# Evergreen.net
KiCad netlist of a schematic drawn in EAGLE
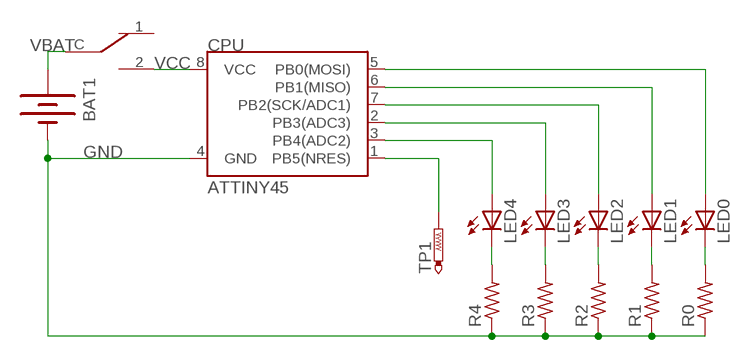
[diagram p0: schematic, sheet 1]

(export (version "E")
  (design (tool "Eeschema 10.0.6"))
  (components
    (comp (ref "BAT1")
      (value "BATTERY20SMD")
      (footprint "eagle-import:BATTCON_20MM")
      (libsource (lib "eagle-import") (part "BATTERY20SMD"))
    )
    (comp (ref "CPU")
      (value "ATTINY45")
      (footprint "eagle-import:SO08-EIAJ")
      (libsource (lib "eagle-import") (part "ATTINY45"))
    )
    (comp (ref "LED0")
      (value "LEDCHIP-LED0805")
      (footprint "eagle-import:CHIP-LED0805")
      (libsource (lib "eagle-import") (part "LEDCHIP-LED0805"))
    )
    (comp (ref "LED1")
      (value "LEDCHIP-LED0805")
      (footprint "eagle-import:CHIP-LED0805")
      (libsource (lib "eagle-import") (part "LEDCHIP-LED0805"))
    )
    (comp (ref "LED2")
      (value "LEDCHIP-LED0805")
      (footprint "eagle-import:CHIP-LED0805")
      (libsource (lib "eagle-import") (part "LEDCHIP-LED0805"))
    )
    (comp (ref "LED3")
      (value "LEDCHIP-LED0805")
      (footprint "eagle-import:CHIP-LED0805")
      (libsource (lib "eagle-import") (part "LEDCHIP-LED0805"))
    )
    (comp (ref "LED4")
      (value "LEDCHIP-LED0805")
      (footprint "eagle-import:CHIP-LED0805")
      (libsource (lib "eagle-import") (part "LEDCHIP-LED0805"))
    )
    (comp (ref "R0")
      (value "R-US_M0805")
      (footprint "eagle-import:M0805")
      (libsource (lib "eagle-import") (part "R-US_M0805"))
    )
    (comp (ref "R1")
      (value "R-US_M0805")
      (footprint "eagle-import:M0805")
      (libsource (lib "eagle-import") (part "R-US_M0805"))
    )
    (comp (ref "R2")
      (value "R-US_M0805")
      (footprint "eagle-import:M0805")
      (libsource (lib "eagle-import") (part "R-US_M0805"))
    )
    (comp (ref "R3")
      (value "R-US_M0805")
      (footprint "eagle-import:M0805")
      (libsource (lib "eagle-import") (part "R-US_M0805"))
    )
    (comp (ref "R4")
      (value "R-US_M0805")
      (footprint "eagle-import:M0805")
      (libsource (lib "eagle-import") (part "R-US_M0805"))
    )
    (comp (ref "SWITCH")
      (value "SWITCH-SPDT")
      (footprint "eagle-import:SSAJ120100")
      (libsource (lib "eagle-import") (part "SWITCH-SPDT"))
    )
    (comp (ref "TP1")
      (value "PTR1B2,54")
      (footprint "eagle-import:B2,54")
      (libsource (lib "eagle-import") (part "PTR1B2,54"))
    )
  )
  (nets
    (net (code "1") (name "/GND") (class "Default")
      (node (ref "BAT1") (pin "2") (pinfunction "-_2") (pintype "power_in"))
      (node (ref "CPU") (pin "4") (pinfunction "GND_4") (pintype "bidirectional"))
      (node (ref "R0") (pin "1") (pinfunction "1_1") (pintype "passive"))
      (node (ref "R1") (pin "1") (pinfunction "1_1") (pintype "passive"))
      (node (ref "R2") (pin "1") (pinfunction "1_1") (pintype "passive"))
      (node (ref "R3") (pin "1") (pinfunction "1_1") (pintype "passive"))
      (node (ref "R4") (pin "1") (pinfunction "1_1") (pintype "passive"))
    )
    (net (code "2") (name "/VBAT") (class "Default")
      (node (ref "BAT1") (pin "1") (pinfunction "+_1") (pintype "power_in"))
      (node (ref "BAT1") (pin "3") (pinfunction "+_3") (pintype "power_in"))
      (node (ref "SWITCH") (pin "C") (pinfunction "C_C") (pintype "bidirectional"))
    )
    (net (code "3") (name "/VCC") (class "Default")
      (node (ref "CPU") (pin "8") (pinfunction "VCC_8") (pintype "bidirectional"))
      (node (ref "SWITCH") (pin "2") (pinfunction "2_2") (pintype "bidirectional"))
    )
    (net (code "4") (name "Net-(CPU-PB0(MOSI))") (class "Default")
      (node (ref "CPU") (pin "5") (pinfunction "PB0(MOSI)_5") (pintype "bidirectional"))
      (node (ref "LED0") (pin "A") (pinfunction "A_A") (pintype "passive"))
    )
    (net (code "5") (name "Net-(CPU-PB1(MISO))") (class "Default")
      (node (ref "CPU") (pin "6") (pinfunction "PB1(MISO)_6") (pintype "bidirectional"))
      (node (ref "LED1") (pin "A") (pinfunction "A_A") (pintype "passive"))
    )
    (net (code "6") (name "Net-(CPU-PB2(SCK{slash}ADC1))") (class "Default")
      (node (ref "CPU") (pin "7") (pinfunction "PB2(SCK/ADC1)_7") (pintype "bidirectional"))
      (node (ref "LED2") (pin "A") (pinfunction "A_A") (pintype "passive"))
    )
    (net (code "7") (name "Net-(CPU-PB3(ADC3))") (class "Default")
      (node (ref "CPU") (pin "2") (pinfunction "PB3(ADC3)_2") (pintype "bidirectional"))
      (node (ref "LED3") (pin "A") (pinfunction "A_A") (pintype "passive"))
    )
    (net (code "8") (name "Net-(CPU-PB4(ADC2))") (class "Default")
      (node (ref "CPU") (pin "3") (pinfunction "PB4(ADC2)_3") (pintype "bidirectional"))
      (node (ref "LED4") (pin "A") (pinfunction "A_A") (pintype "passive"))
    )
    (net (code "9") (name "Net-(CPU-PB5(NRES))") (class "Default")
      (node (ref "CPU") (pin "1") (pinfunction "PB5(NRES)_1") (pintype "bidirectional"))
      (node (ref "TP1") (pin "TP") (pinfunction "TP_TP") (pintype "input"))
    )
    (net (code "10") (name "Net-(LED0-PadC)") (class "Default")
      (node (ref "LED0") (pin "C") (pinfunction "C_C") (pintype "passive"))
      (node (ref "R0") (pin "2") (pinfunction "2_2") (pintype "passive"))
    )
    (net (code "11") (name "Net-(LED1-PadC)") (class "Default")
      (node (ref "LED1") (pin "C") (pinfunction "C_C") (pintype "passive"))
      (node (ref "R1") (pin "2") (pinfunction "2_2") (pintype "passive"))
    )
    (net (code "12") (name "Net-(LED2-PadC)") (class "Default")
      (node (ref "LED2") (pin "C") (pinfunction "C_C") (pintype "passive"))
      (node (ref "R2") (pin "2") (pinfunction "2_2") (pintype "passive"))
    )
    (net (code "13") (name "Net-(LED3-PadC)") (class "Default")
      (node (ref "LED3") (pin "C") (pinfunction "C_C") (pintype "passive"))
      (node (ref "R3") (pin "2") (pinfunction "2_2") (pintype "passive"))
    )
    (net (code "14") (name "Net-(LED4-PadC)") (class "Default")
      (node (ref "LED4") (pin "C") (pinfunction "C_C") (pintype "passive"))
      (node (ref "R4") (pin "2") (pinfunction "2_2") (pintype "passive"))
    )
    (net (code "15") (name "unconnected-(SWITCH-Pad1)") (class "Default")
      (node (ref "SWITCH") (pin "1") (pinfunction "1_1") (pintype "bidirectional"))
    )
  )
)
